# OpenBook_v3.net
KiCad netlist of a schematic drawn in EAGLE
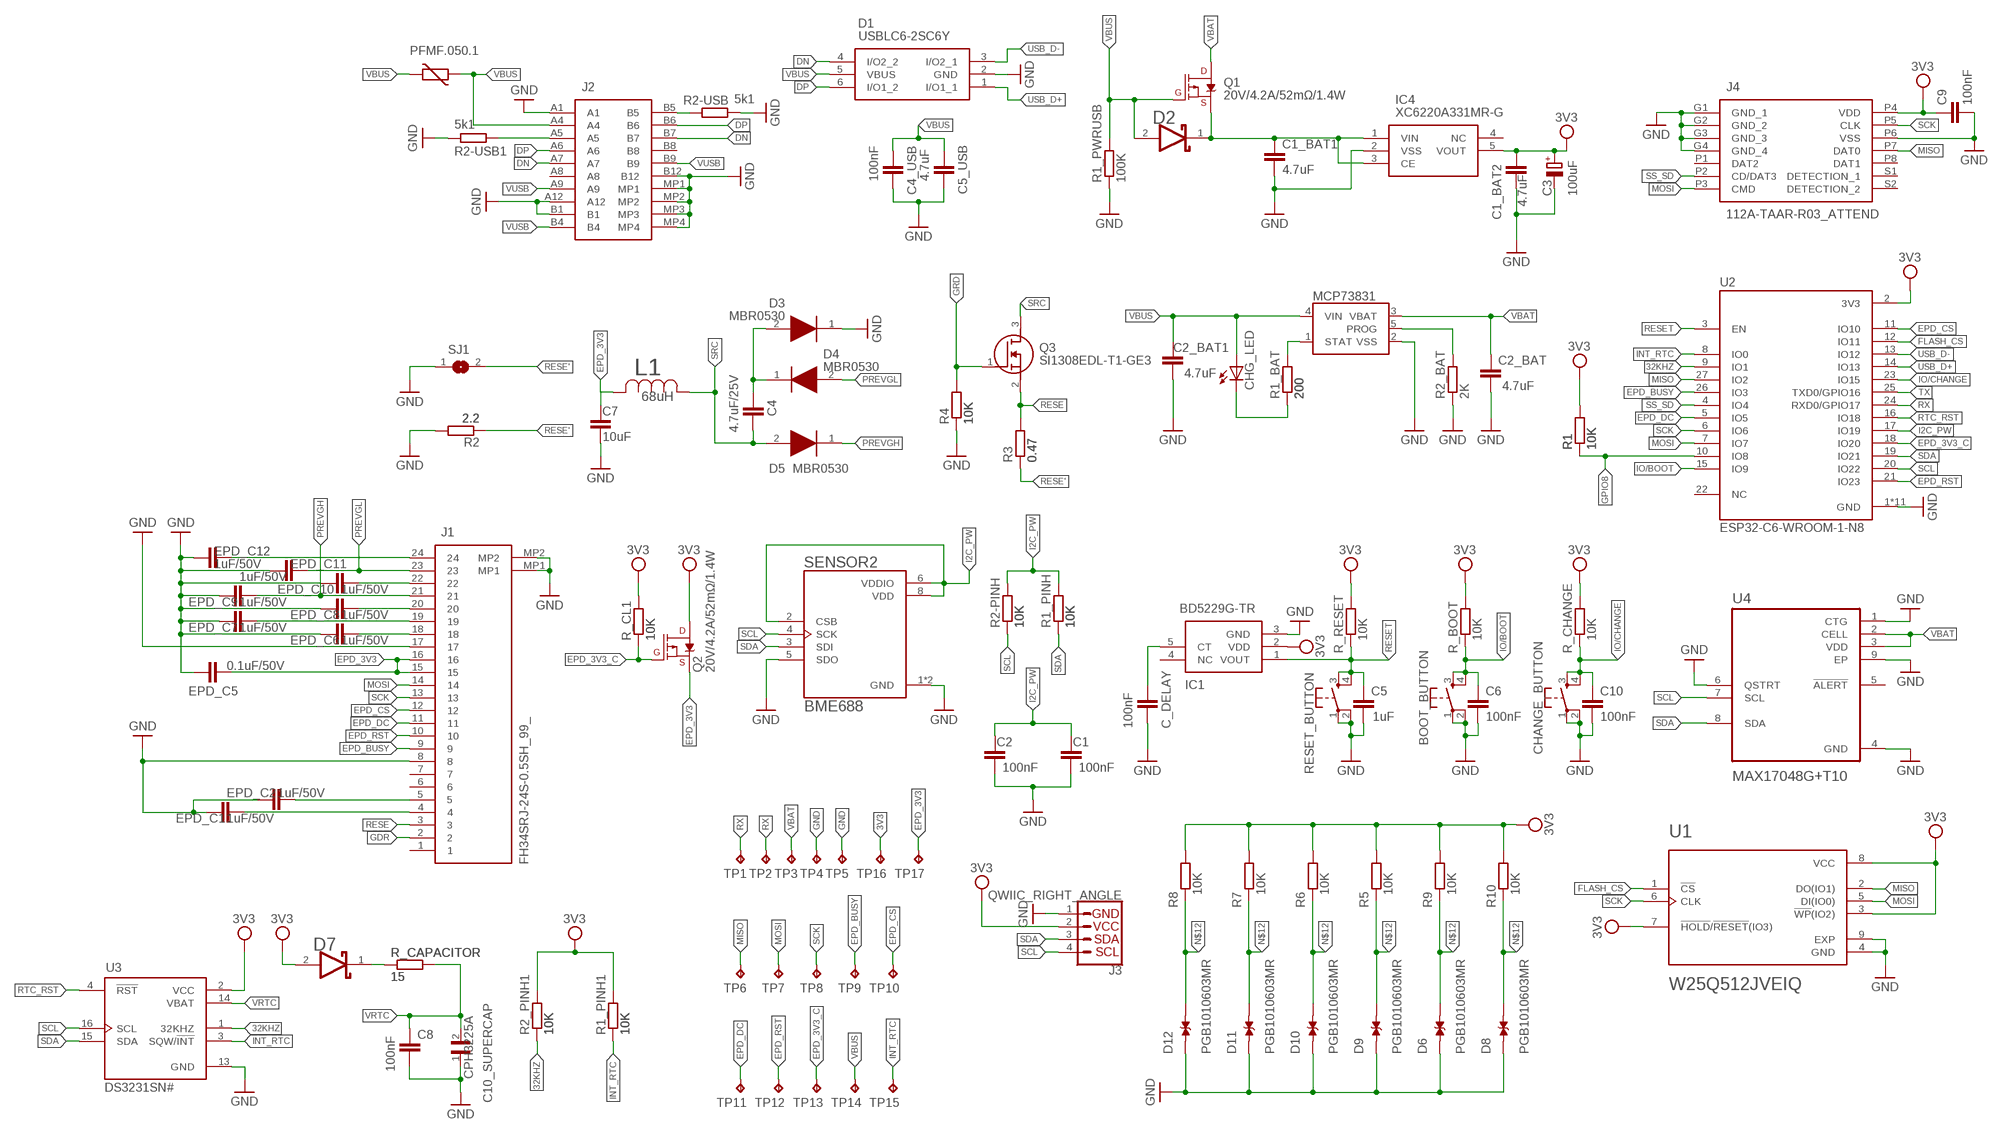
[diagram p0: schematic, sheet 1]

(export (version "E")
  (design (tool "Eeschema 10.0.6"))
  (components
    (comp (ref "BOOT_BUTTON")
      (value "BUTTON_CUSYOMV1")
      (footprint "eagle-import:MYBUTTON")
      (libsource (lib "eagle-import") (part "BUTTON_CUSYOMV1"))
    )
    (comp (ref "C1")
      (value "100nF")
      (footprint "eagle-import:ESP32_WROVER_EAGLE-LTSPICE_C0402")
      (libsource (lib "eagle-import") (part "ESP32_WROVER_EAGLE-LTSPICE_CC0402"))
    )
    (comp (ref "C1_BAT1")
      (value "4.7uF")
      (footprint "eagle-import:ESP32_WROVER_EAGLE-LTSPICE_C0402")
      (libsource (lib "eagle-import") (part "ESP32_WROVER_EAGLE-LTSPICE_CC0402"))
    )
    (comp (ref "C1_BAT2")
      (value "4.7uF")
      (footprint "eagle-import:ESP32_WROVER_EAGLE-LTSPICE_C0402")
      (libsource (lib "eagle-import") (part "ESP32_WROVER_EAGLE-LTSPICE_CC0402"))
    )
    (comp (ref "C2")
      (value "100nF")
      (footprint "eagle-import:ESP32_WROVER_EAGLE-LTSPICE_C0402")
      (libsource (lib "eagle-import") (part "ESP32_WROVER_EAGLE-LTSPICE_CC0402"))
    )
    (comp (ref "C2_BAT")
      (value "4.7uF")
      (footprint "eagle-import:ESP32_WROVER_EAGLE-LTSPICE_C0402")
      (libsource (lib "eagle-import") (part "ESP32_WROVER_EAGLE-LTSPICE_CC0402"))
    )
    (comp (ref "C2_BAT1")
      (value "4.7uF")
      (footprint "eagle-import:ESP32_WROVER_EAGLE-LTSPICE_C0402")
      (libsource (lib "eagle-import") (part "ESP32_WROVER_EAGLE-LTSPICE_CC0402"))
    )
    (comp (ref "C3")
      (value "100uF")
      (footprint "eagle-import:RCL_CT3528")
      (libsource (lib "eagle-import") (part "RCL_CPOL-EUCT3528"))
    )
    (comp (ref "C4")
      (value "4.7uF/25V")
      (footprint "eagle-import:ESP32_WROVER_EAGLE-LTSPICE_C0402")
      (libsource (lib "eagle-import") (part "ESP32_WROVER_EAGLE-LTSPICE_CC0402"))
    )
    (comp (ref "C4_USB")
      (value "100nF")
      (footprint "eagle-import:ESP32_WROVER_EAGLE-LTSPICE_C0402")
      (libsource (lib "eagle-import") (part "ESP32_WROVER_EAGLE-LTSPICE_CC0402"))
    )
    (comp (ref "C5")
      (value "1uF")
      (footprint "eagle-import:ESP32_WROVER_EAGLE-LTSPICE_C0402")
      (libsource (lib "eagle-import") (part "ESP32_WROVER_EAGLE-LTSPICE_CC0402"))
    )
    (comp (ref "C5_USB")
      (value "4.7uF")
      (footprint "eagle-import:ESP32_WROVER_EAGLE-LTSPICE_C0402")
      (libsource (lib "eagle-import") (part "ESP32_WROVER_EAGLE-LTSPICE_CC0402"))
    )
    (comp (ref "C6")
      (value "100nF")
      (footprint "eagle-import:ESP32_WROVER_EAGLE-LTSPICE_C0402")
      (libsource (lib "eagle-import") (part "ESP32_WROVER_EAGLE-LTSPICE_CC0402"))
    )
    (comp (ref "C7")
      (value "10uF")
      (footprint "eagle-import:ESP32_WROVER_EAGLE-LTSPICE_C0402")
      (libsource (lib "eagle-import") (part "ESP32_WROVER_EAGLE-LTSPICE_CC0402"))
    )
    (comp (ref "C8")
      (value "100nF")
      (footprint "eagle-import:ESP32_WROVER_EAGLE-LTSPICE_C0402")
      (libsource (lib "eagle-import") (part "ESP32_WROVER_EAGLE-LTSPICE_CC0402"))
    )
    (comp (ref "C9")
      (value "100nF")
      (footprint "eagle-import:ESP32_WROVER_EAGLE-LTSPICE_C0402")
      (libsource (lib "eagle-import") (part "ESP32_WROVER_EAGLE-LTSPICE_CC0402"))
    )
    (comp (ref "C10")
      (value "100nF")
      (footprint "eagle-import:ESP32_WROVER_EAGLE-LTSPICE_C0402")
      (libsource (lib "eagle-import") (part "ESP32_WROVER_EAGLE-LTSPICE_CC0402"))
    )
    (comp (ref "C10_SUPERCAP")
      (value "CPH3225A")
      (footprint "eagle-import:CAPCP3225X100N")
      (fields (field (name "MF") "Seiko Instruments"))
      (libsource (lib "eagle-import") (part "CPH3225A"))
    )
    (comp (ref "CHANGE_BUTTON")
      (value "BUTTON_CUSYOMV1")
      (footprint "eagle-import:MYBUTTON")
      (libsource (lib "eagle-import") (part "BUTTON_CUSYOMV1"))
    )
    (comp (ref "CHG_LED")
      (value "ADAFRUIT_LEDCHIP-LED0603")
      (footprint "eagle-import:ADAFRUIT_CHIP-LED0603")
      (libsource (lib "eagle-import") (part "ADAFRUIT_LEDCHIP-LED0603"))
    )
    (comp (ref "C_DELAY")
      (value "100nF")
      (footprint "eagle-import:ESP32_WROVER_EAGLE-LTSPICE_C0402")
      (libsource (lib "eagle-import") (part "ESP32_WROVER_EAGLE-LTSPICE_CC0402"))
    )
    (comp (ref "D1")
      (value "USBLC6-2SC6Y")
      (footprint "eagle-import:SOT95P280X145-6N")
      (fields (field (name "MF") "STMicroelectronics"))
      (libsource (lib "eagle-import") (part "USBLC6-2SC6Y"))
    )
    (comp (ref "D2")
      (value "ESP32_WROVER_AVX---SD0805S020S1R0_AVX_SD0805S020S1R0_0_0AVX_SD0805S020S1R0_0_0")
      (footprint "eagle-import:ESP32_WROVER_AVX---SD0805S020S1R0_AVX_SD0805S020S1R0_0")
      (fields
        (field (name "DIGIKEY_PART_NUMBER") "478-7800-1-ND")
        (field (name "MF") "AVX")
        (field (name "MOUSER_PART_NUMBER") "581-SD0805S020S1R0")
      )
      (libsource (lib "eagle-import") (part "ESP32_WROVER_AVX---SD0805S020S1R0_AVX_SD0805S020S1R0_0_0AVX_SD0805S020S1R0_0_0"))
    )
    (comp (ref "D3")
      (value "MBR0530")
      (footprint "eagle-import:SOD3716X135N")
      (fields (field (name "MF") "ON Semiconductor"))
      (libsource (lib "eagle-import") (part "MBR0530"))
    )
    (comp (ref "D4")
      (value "MBR0530")
      (footprint "eagle-import:SOD3716X135N")
      (fields (field (name "MF") "ON Semiconductor"))
      (libsource (lib "eagle-import") (part "MBR0530"))
    )
    (comp (ref "D5")
      (value "MBR0530")
      (footprint "eagle-import:SOD3716X135N")
      (fields (field (name "MF") "ON Semiconductor"))
      (libsource (lib "eagle-import") (part "MBR0530"))
    )
    (comp (ref "D6")
      (value "PGB1010603MR")
      (footprint "eagle-import:DIOC1608X36N")
      (fields (field (name "MF") "Littelfuse Inc."))
      (libsource (lib "eagle-import") (part "PGB1010603MR"))
    )
    (comp (ref "D7")
      (value "ESP32_WROVER_AVX---SD0805S020S1R0_AVX_SD0805S020S1R0_0_0AVX_SD0805S020S1R0_0_0")
      (footprint "eagle-import:ESP32_WROVER_AVX---SD0805S020S1R0_AVX_SD0805S020S1R0_0")
      (fields
        (field (name "DIGIKEY_PART_NUMBER") "478-7800-1-ND")
        (field (name "MF") "AVX")
        (field (name "MOUSER_PART_NUMBER") "581-SD0805S020S1R0")
      )
      (libsource (lib "eagle-import") (part "ESP32_WROVER_AVX---SD0805S020S1R0_AVX_SD0805S020S1R0_0_0AVX_SD0805S020S1R0_0_0"))
    )
    (comp (ref "D8")
      (value "PGB1010603MR")
      (footprint "eagle-import:DIOC1608X36N")
      (fields (field (name "MF") "Littelfuse Inc."))
      (libsource (lib "eagle-import") (part "PGB1010603MR"))
    )
    (comp (ref "D9")
      (value "PGB1010603MR")
      (footprint "eagle-import:DIOC1608X36N")
      (fields (field (name "MF") "Littelfuse Inc."))
      (libsource (lib "eagle-import") (part "PGB1010603MR"))
    )
    (comp (ref "D10")
      (value "PGB1010603MR")
      (footprint "eagle-import:DIOC1608X36N")
      (fields (field (name "MF") "Littelfuse Inc."))
      (libsource (lib "eagle-import") (part "PGB1010603MR"))
    )
    (comp (ref "D11")
      (value "PGB1010603MR")
      (footprint "eagle-import:DIOC1608X36N")
      (fields (field (name "MF") "Littelfuse Inc."))
      (libsource (lib "eagle-import") (part "PGB1010603MR"))
    )
    (comp (ref "D12")
      (value "PGB1010603MR")
      (footprint "eagle-import:DIOC1608X36N")
      (fields (field (name "MF") "Littelfuse Inc."))
      (libsource (lib "eagle-import") (part "PGB1010603MR"))
    )
    (comp (ref "EPD_C1")
      (value "1uF/50V")
      (footprint "eagle-import:ESP32_WROVER_EAGLE-LTSPICE_C0402")
      (libsource (lib "eagle-import") (part "ESP32_WROVER_EAGLE-LTSPICE_CC0402"))
    )
    (comp (ref "EPD_C2")
      (value "1uF/50V")
      (footprint "eagle-import:ESP32_WROVER_EAGLE-LTSPICE_C0402")
      (libsource (lib "eagle-import") (part "ESP32_WROVER_EAGLE-LTSPICE_CC0402"))
    )
    (comp (ref "EPD_C5")
      (value "0.1uF/50V")
      (footprint "eagle-import:ESP32_WROVER_EAGLE-LTSPICE_C0402")
      (libsource (lib "eagle-import") (part "ESP32_WROVER_EAGLE-LTSPICE_CC0402"))
    )
    (comp (ref "EPD_C6")
      (value "1uF/50V")
      (footprint "eagle-import:ESP32_WROVER_EAGLE-LTSPICE_C0402")
      (libsource (lib "eagle-import") (part "ESP32_WROVER_EAGLE-LTSPICE_CC0402"))
    )
    (comp (ref "EPD_C7")
      (value "1uF/50V")
      (footprint "eagle-import:ESP32_WROVER_EAGLE-LTSPICE_C0402")
      (libsource (lib "eagle-import") (part "ESP32_WROVER_EAGLE-LTSPICE_CC0402"))
    )
    (comp (ref "EPD_C8")
      (value "1uF/50V")
      (footprint "eagle-import:ESP32_WROVER_EAGLE-LTSPICE_C0402")
      (libsource (lib "eagle-import") (part "ESP32_WROVER_EAGLE-LTSPICE_CC0402"))
    )
    (comp (ref "EPD_C9")
      (value "1uF/50V")
      (footprint "eagle-import:ESP32_WROVER_EAGLE-LTSPICE_C0402")
      (libsource (lib "eagle-import") (part "ESP32_WROVER_EAGLE-LTSPICE_CC0402"))
    )
    (comp (ref "EPD_C10")
      (value "1uF/50V")
      (footprint "eagle-import:ESP32_WROVER_EAGLE-LTSPICE_C0402")
      (libsource (lib "eagle-import") (part "ESP32_WROVER_EAGLE-LTSPICE_CC0402"))
    )
    (comp (ref "EPD_C11")
      (value "1uF/50V")
      (footprint "eagle-import:ESP32_WROVER_EAGLE-LTSPICE_C0402")
      (libsource (lib "eagle-import") (part "ESP32_WROVER_EAGLE-LTSPICE_CC0402"))
    )
    (comp (ref "EPD_C12")
      (value "1uF/50V")
      (footprint "eagle-import:ESP32_WROVER_EAGLE-LTSPICE_C0402")
      (libsource (lib "eagle-import") (part "ESP32_WROVER_EAGLE-LTSPICE_CC0402"))
    )
    (comp (ref "IC1")
      (value "BD5229G-TR")
      (footprint "eagle-import:SOT95P280X125-5N")
      (fields (field (name "MOUSER_PART_NUMBER") "755-BD5229G-TR"))
      (libsource (lib "eagle-import") (part "BD5229G-TR"))
    )
    (comp (ref "IC4")
      (value "XC6220A331MR-G")
      (footprint "eagle-import:SOT95P280X120-5N")
      (fields (field (name "MOUSER_PART_NUMBER") "865-XC6220A331MR-G"))
      (libsource (lib "eagle-import") (part "XC6220A331MR-G"))
    )
    (comp (ref "J1")
      (value "FH34SRJ-24S-0.5SH_99_")
      (footprint "eagle-import:FH34SRJ24S05SH99")
      (fields
        (field (name "MANUFACTURER_PART_NUMBER") "FH34SRJ-24S-0.5SH(99)")
        (field (name "MOUSER_PART_NUMBER") "798-FH34SRJ24S05SH99")
      )
      (libsource (lib "eagle-import") (part "FH34SRJ-24S-0.5SH_99_"))
    )
    (comp (ref "J2")
      (value "SAMACSYS_PARTS_USB4110-GF-A")
      (footprint "eagle-import:SAMACSYS_PARTS_USB4110GFA")
      (fields
        (field (name "MANUFACTURER_PART_NUMBER") "USB4110-GF-A")
        (field (name "MOUSER_PART_NUMBER") "640-USB4110-GF-A")
      )
      (libsource (lib "eagle-import") (part "SAMACSYS_PARTS_USB4110-GF-A"))
    )
    (comp (ref "J3")
      (value "QWIIC_RIGHT_ANGLE")
      (footprint "eagle-import:JST04_1MM_RA")
      (libsource (lib "eagle-import") (part "QWIIC_CONNECTORJS-1MM"))
    )
    (comp (ref "J4")
      (value "112A-TAAR-R03_ATTEND")
      (footprint "eagle-import:112ATAARR03ATTEND")
      (fields (field (name "MANUFACTURER_PART_NUMBER") "112A-TAAR-R03 ATTEND"))
      (libsource (lib "eagle-import") (part "112A-TAAR-R03_ATTEND"))
    )
    (comp (ref "L1")
      (value "68uH")
      (footprint "eagle-import:IND_4828-WE-TPC_WRE")
      (fields
        (field (name "MANUFACTURER_PART_NUMBER") "744043680")
        (field (name "COPYRIGHT") "Copyright (C) 2024 Ultra Librarian. All rights reserved.")
      )
      (libsource (lib "eagle-import") (part "744043680IND_4828-WE-TPC_WRE"))
    )
    (comp (ref "MCP73831")
      (value "ESP32_WROVER_SPARKFUN-IC-POWER_MCP73831")
      (footprint "eagle-import:ESP32_WROVER_SPARKFUN-IC-POWER_SOT23-5")
      (libsource (lib "eagle-import") (part "ESP32_WROVER_SPARKFUN-IC-POWER_MCP73831"))
    )
    (comp (ref "PFMF.050.1")
      (value "ESP32C6_VARISTORCN1812")
      (footprint "eagle-import:ESP32C6_VARISTOR_CT_CN1812")
      (libsource (lib "eagle-import") (part "ESP32C6_VARISTORCN1812"))
    )
    (comp (ref "Q1")
      (value "20V/4.2A/52mΩ/1.4W")
      (footprint "eagle-import:ESP32_WROVER_SPARKFUN-DISCRETESEMI_SOT23-3")
      (libsource (lib "eagle-import") (part "ESP32_WROVER_SPARKFUN-DISCRETESEMI_MOSFET_PCH-DMG2305UX-7"))
    )
    (comp (ref "Q2")
      (value "20V/4.2A/52mΩ/1.4W")
      (footprint "eagle-import:ESP32_WROVER_SPARKFUN-DISCRETESEMI_SOT23-3")
      (libsource (lib "eagle-import") (part "ESP32_WROVER_SPARKFUN-DISCRETESEMI_MOSFET_PCH-DMG2305UX-7"))
    )
    (comp (ref "Q3")
      (value "SI1308EDL-T1-GE3")
      (footprint "eagle-import:SOT65P210X110-3N")
      (fields (field (name "MF") "Vishay Siliconix"))
      (libsource (lib "eagle-import") (part "SI1308EDL-T1-GE3"))
    )
    (comp (ref "R1")
      (value "10K")
      (footprint "eagle-import:ESP32_WROVER_EAGLE-LTSPICE_R0402")
      (libsource (lib "eagle-import") (part "ESP32_WROVER_EAGLE-LTSPICE_RR0402"))
    )
    (comp (ref "R1_BAT")
      (value "200")
      (footprint "eagle-import:ESP32_WROVER_EAGLE-LTSPICE_R0402")
      (libsource (lib "eagle-import") (part "ESP32_WROVER_EAGLE-LTSPICE_RR0402"))
    )
    (comp (ref "R1_PINH")
      (value "10K")
      (footprint "eagle-import:ESP32_WROVER_EAGLE-LTSPICE_R0402")
      (libsource (lib "eagle-import") (part "ESP32_WROVER_EAGLE-LTSPICE_RR0402"))
    )
    (comp (ref "R1_PINH1")
      (value "10K")
      (footprint "eagle-import:ESP32_WROVER_EAGLE-LTSPICE_R0402")
      (libsource (lib "eagle-import") (part "ESP32_WROVER_EAGLE-LTSPICE_RR0402"))
    )
    (comp (ref "R1_PWRUSB")
      (value "100K")
      (footprint "eagle-import:ESP32_WROVER_EAGLE-LTSPICE_R0402")
      (libsource (lib "eagle-import") (part "ESP32_WROVER_EAGLE-LTSPICE_RR0402"))
    )
    (comp (ref "R2")
      (value "2.2")
      (footprint "eagle-import:ESP32_WROVER_EAGLE-LTSPICE_R0402")
      (libsource (lib "eagle-import") (part "ESP32_WROVER_EAGLE-LTSPICE_RR0402"))
    )
    (comp (ref "R2-PINH")
      (value "10K")
      (footprint "eagle-import:ESP32_WROVER_EAGLE-LTSPICE_R0402")
      (libsource (lib "eagle-import") (part "ESP32_WROVER_EAGLE-LTSPICE_RR0402"))
    )
    (comp (ref "R2-USB")
      (value "5k1")
      (footprint "eagle-import:ESP32_WROVER_EAGLE-LTSPICE_R0402")
      (libsource (lib "eagle-import") (part "ESP32_WROVER_EAGLE-LTSPICE_RR0402"))
    )
    (comp (ref "R2-USB1")
      (value "5k1")
      (footprint "eagle-import:ESP32_WROVER_EAGLE-LTSPICE_R0402")
      (libsource (lib "eagle-import") (part "ESP32_WROVER_EAGLE-LTSPICE_RR0402"))
    )
    (comp (ref "R2_BAT")
      (value "2K")
      (footprint "eagle-import:ESP32_WROVER_EAGLE-LTSPICE_R0402")
      (libsource (lib "eagle-import") (part "ESP32_WROVER_EAGLE-LTSPICE_RR0402"))
    )
    (comp (ref "R2_PINH1")
      (value "10K")
      (footprint "eagle-import:ESP32_WROVER_EAGLE-LTSPICE_R0402")
      (libsource (lib "eagle-import") (part "ESP32_WROVER_EAGLE-LTSPICE_RR0402"))
    )
    (comp (ref "R3")
      (value "0.47")
      (footprint "eagle-import:ESP32_WROVER_EAGLE-LTSPICE_R0402")
      (libsource (lib "eagle-import") (part "ESP32_WROVER_EAGLE-LTSPICE_RR0402"))
    )
    (comp (ref "R4")
      (value "10K")
      (footprint "eagle-import:ESP32_WROVER_EAGLE-LTSPICE_R0402")
      (libsource (lib "eagle-import") (part "ESP32_WROVER_EAGLE-LTSPICE_RR0402"))
    )
    (comp (ref "R5")
      (value "10K")
      (footprint "eagle-import:ESP32_WROVER_EAGLE-LTSPICE_R0402")
      (libsource (lib "eagle-import") (part "ESP32_WROVER_EAGLE-LTSPICE_RR0402"))
    )
    (comp (ref "R6")
      (value "10K")
      (footprint "eagle-import:ESP32_WROVER_EAGLE-LTSPICE_R0402")
      (libsource (lib "eagle-import") (part "ESP32_WROVER_EAGLE-LTSPICE_RR0402"))
    )
    (comp (ref "R7")
      (value "10K")
      (footprint "eagle-import:ESP32_WROVER_EAGLE-LTSPICE_R0402")
      (libsource (lib "eagle-import") (part "ESP32_WROVER_EAGLE-LTSPICE_RR0402"))
    )
    (comp (ref "R8")
      (value "10K")
      (footprint "eagle-import:ESP32_WROVER_EAGLE-LTSPICE_R0402")
      (libsource (lib "eagle-import") (part "ESP32_WROVER_EAGLE-LTSPICE_RR0402"))
    )
    (comp (ref "R9")
      (value "10K")
      (footprint "eagle-import:ESP32_WROVER_EAGLE-LTSPICE_R0402")
      (libsource (lib "eagle-import") (part "ESP32_WROVER_EAGLE-LTSPICE_RR0402"))
    )
    (comp (ref "R10")
      (value "10K")
      (footprint "eagle-import:ESP32_WROVER_EAGLE-LTSPICE_R0402")
      (libsource (lib "eagle-import") (part "ESP32_WROVER_EAGLE-LTSPICE_RR0402"))
    )
    (comp (ref "RESET_BUTTON")
      (value "BUTTON_CUSYOMV1")
      (footprint "eagle-import:MYBUTTON")
      (libsource (lib "eagle-import") (part "BUTTON_CUSYOMV1"))
    )
    (comp (ref "R_BOOT")
      (value "10K")
      (footprint "eagle-import:ESP32_WROVER_EAGLE-LTSPICE_R0402")
      (libsource (lib "eagle-import") (part "ESP32_WROVER_EAGLE-LTSPICE_RR0402"))
    )
    (comp (ref "R_CAPACITOR")
      (value "15")
      (footprint "eagle-import:ESP32_WROVER_EAGLE-LTSPICE_R0402")
      (libsource (lib "eagle-import") (part "ESP32_WROVER_EAGLE-LTSPICE_RR0402"))
    )
    (comp (ref "R_CHANGE")
      (value "10K")
      (footprint "eagle-import:ESP32_WROVER_EAGLE-LTSPICE_R0402")
      (libsource (lib "eagle-import") (part "ESP32_WROVER_EAGLE-LTSPICE_RR0402"))
    )
    (comp (ref "R_CL1")
      (value "10K")
      (footprint "eagle-import:ESP32_WROVER_EAGLE-LTSPICE_R0402")
      (libsource (lib "eagle-import") (part "ESP32_WROVER_EAGLE-LTSPICE_RR0402"))
    )
    (comp (ref "R_RESET")
      (value "10K")
      (footprint "eagle-import:ESP32_WROVER_EAGLE-LTSPICE_R0402")
      (libsource (lib "eagle-import") (part "ESP32_WROVER_EAGLE-LTSPICE_RR0402"))
    )
    (comp (ref "SENSOR2")
      (value "BME688")
      (footprint "eagle-import:ESP32_WROVER_BME680_PSON80P300X300X100-8N")
      (fields (field (name "MF") "Bosch Sensortec") (field (name "MP") "BME680"))
      (libsource (lib "eagle-import") (part "ESP32_WROVER_BME680_BME680"))
    )
    (comp (ref "SJ1") (value "SJ") (footprint "eagle-import:SJ") (libsource (lib "eagle-import") (part "SJ")))
    (comp (ref "TP1")
      (value "TPTP20R")
      (footprint "eagle-import:TP20R")
      (libsource (lib "eagle-import") (part "TPTP20R"))
    )
    (comp (ref "TP2")
      (value "TPTP20R")
      (footprint "eagle-import:TP20R")
      (libsource (lib "eagle-import") (part "TPTP20R"))
    )
    (comp (ref "TP3")
      (value "TPTP20R")
      (footprint "eagle-import:TP20R")
      (libsource (lib "eagle-import") (part "TPTP20R"))
    )
    (comp (ref "TP4")
      (value "TPTP20R")
      (footprint "eagle-import:TP20R")
      (libsource (lib "eagle-import") (part "TPTP20R"))
    )
    (comp (ref "TP5")
      (value "TPTP20R")
      (footprint "eagle-import:TP20R")
      (libsource (lib "eagle-import") (part "TPTP20R"))
    )
    (comp (ref "TP6")
      (value "TPTP20R")
      (footprint "eagle-import:TP20R")
      (libsource (lib "eagle-import") (part "TPTP20R"))
    )
    (comp (ref "TP7")
      (value "TPTP20R")
      (footprint "eagle-import:TP20R")
      (libsource (lib "eagle-import") (part "TPTP20R"))
    )
    (comp (ref "TP8")
      (value "TPTP20R")
      (footprint "eagle-import:TP20R")
      (libsource (lib "eagle-import") (part "TPTP20R"))
    )
    (comp (ref "TP9")
      (value "TPTP20R")
      (footprint "eagle-import:TP20R")
      (libsource (lib "eagle-import") (part "TPTP20R"))
    )
    (comp (ref "TP10")
      (value "TPTP20R")
      (footprint "eagle-import:TP20R")
      (libsource (lib "eagle-import") (part "TPTP20R"))
    )
    (comp (ref "TP11")
      (value "TPTP20R")
      (footprint "eagle-import:TP20R")
      (libsource (lib "eagle-import") (part "TPTP20R"))
    )
    (comp (ref "TP12")
      (value "TPTP20R")
      (footprint "eagle-import:TP20R")
      (libsource (lib "eagle-import") (part "TPTP20R"))
    )
    (comp (ref "TP13")
      (value "TPTP20R")
      (footprint "eagle-import:TP20R")
      (libsource (lib "eagle-import") (part "TPTP20R"))
    )
    (comp (ref "TP14")
      (value "TPTP20R")
      (footprint "eagle-import:TP20R")
      (libsource (lib "eagle-import") (part "TPTP20R"))
    )
    (comp (ref "TP15")
      (value "TPTP20R")
      (footprint "eagle-import:TP20R")
      (libsource (lib "eagle-import") (part "TPTP20R"))
    )
    (comp (ref "TP16")
      (value "TPTP20R")
      (footprint "eagle-import:TP20R")
      (libsource (lib "eagle-import") (part "TPTP20R"))
    )
    (comp (ref "TP17")
      (value "TPTP20R")
      (footprint "eagle-import:TP20R")
      (libsource (lib "eagle-import") (part "TPTP20R"))
    )
    (comp (ref "U1")
      (value "W25Q512JVEIQ")
      (footprint "eagle-import:SON127P600X800X80-9N")
      (fields (field (name "MF") "Winbond Electronics"))
      (libsource (lib "eagle-import") (part "W25Q512JVEIQ"))
    )
    (comp (ref "U2")
      (value "ESP32-C6-WROOM-1-N8")
      (footprint "eagle-import:XCVR_ESP32-C6-WROOM-1-N8")
      (fields (field (name "MF") "Espressif Systems"))
      (libsource (lib "eagle-import") (part "ESP32-C6-WROOM-1-N8"))
    )
    (comp (ref "U3")
      (value "DS3231SN#")
      (footprint "eagle-import:SOIC127P1032X265-16N")
      (fields (field (name "MF") "Analog Devices"))
      (libsource (lib "eagle-import") (part "DS3231SN#"))
    )
    (comp (ref "U4")
      (value "MAX17048G+T10")
      (footprint "eagle-import:SON50P200X200X80-9N")
      (fields (field (name "MF") "Analog Devices"))
      (libsource (lib "eagle-import") (part "MAX17048G+T10"))
    )
  )
  (nets
    (net (code "1") (name "3V3") (class "Default")
      (node (ref "C1_BAT2") (pin "1") (pinfunction "1_1") (pintype "passive"))
      (node (ref "C3") (pin "+") (pinfunction "+_+") (pintype "passive"))
      (node (ref "C9") (pin "1") (pinfunction "1_1") (pintype "passive"))
      (node (ref "D7") (pin "2") (pinfunction "ANODE_2") (pintype "bidirectional"))
      (node (ref "IC1") (pin "2") (pinfunction "VDD_2") (pintype "bidirectional"))
      (node (ref "IC4") (pin "5") (pinfunction "VOUT_5") (pintype "bidirectional"))
      (node (ref "J3") (pin "2") (pinfunction "2_2") (pintype "power_in"))
      (node (ref "J4") (pin "P4") (pinfunction "VDD_P4") (pintype "bidirectional"))
      (node (ref "Q2") (pin "3") (pinfunction "D_3") (pintype "bidirectional"))
      (node (ref "R1") (pin "2") (pinfunction "2_2") (pintype "passive"))
      (node (ref "R10") (pin "2") (pinfunction "2_2") (pintype "passive"))
      (node (ref "R1_PINH1") (pin "2") (pinfunction "2_2") (pintype "passive"))
      (node (ref "R2_PINH1") (pin "2") (pinfunction "2_2") (pintype "passive"))
      (node (ref "R5") (pin "2") (pinfunction "2_2") (pintype "passive"))
      (node (ref "R6") (pin "2") (pinfunction "2_2") (pintype "passive"))
      (node (ref "R7") (pin "2") (pinfunction "2_2") (pintype "passive"))
      (node (ref "R8") (pin "2") (pinfunction "2_2") (pintype "passive"))
      (node (ref "R9") (pin "2") (pinfunction "2_2") (pintype "passive"))
      (node (ref "R_BOOT") (pin "2") (pinfunction "2_2") (pintype "passive"))
      (node (ref "R_CHANGE") (pin "2") (pinfunction "2_2") (pintype "passive"))
      (node (ref "R_CL1") (pin "2") (pinfunction "2_2") (pintype "passive"))
      (node (ref "R_RESET") (pin "2") (pinfunction "2_2") (pintype "passive"))
      (node (ref "TP16") (pin "TP") (pinfunction "TP_TP") (pintype "input"))
      (node (ref "U1") (pin "3") (pinfunction "~{WP}(IO2)_3") (pintype "bidirectional"))
      (node (ref "U1") (pin "7") (pinfunction "~{HOLD}/~{RESET}(IO3)_7") (pintype "bidirectional"))
      (node (ref "U1") (pin "8") (pinfunction "VCC_8") (pintype "power_in"))
      (node (ref "U2") (pin "2") (pinfunction "3V3_2") (pintype "power_in"))
      (node (ref "U3") (pin "2") (pinfunction "VCC_2") (pintype "power_in"))
    )
    (net (code "2") (name "32KHZ") (class "Default")
      (node (ref "R2_PINH1") (pin "1") (pinfunction "1_1") (pintype "passive"))
      (node (ref "U2") (pin "9") (pinfunction "IO1_9") (pintype "bidirectional"))
      (node (ref "U3") (pin "1") (pinfunction "32KHZ_1") (pintype "output"))
    )
    (net (code "3") (name "DN") (class "Default")
      (node (ref "D1") (pin "4") (pinfunction "I/O2_2_4") (pintype "bidirectional"))
      (node (ref "J2") (pin "A7") (pinfunction "A7_A7") (pintype "bidirectional"))
      (node (ref "J2") (pin "B7") (pinfunction "B7_B7") (pintype "bidirectional"))
    )
    (net (code "4") (name "DP") (class "Default")
      (node (ref "D1") (pin "6") (pinfunction "I/O1_2_6") (pintype "bidirectional"))
      (node (ref "J2") (pin "A6") (pinfunction "A6_A6") (pintype "bidirectional"))
      (node (ref "J2") (pin "B6") (pinfunction "B6_B6") (pintype "bidirectional"))
    )
    (net (code "5") (name "EPD_3V3") (class "Default")
      (node (ref "C7") (pin "1") (pinfunction "1_1") (pintype "passive"))
      (node (ref "EPD_C5") (pin "2") (pinfunction "2_2") (pintype "passive"))
      (node (ref "J1") (pin "15") (pinfunction "15_15") (pintype "bidirectional"))
      (node (ref "J1") (pin "16") (pinfunction "16_16") (pintype "bidirectional"))
      (node (ref "L1") (pin "2") (pinfunction "2_2") (pintype "passive"))
      (node (ref "Q2") (pin "2") (pinfunction "S_2") (pintype "bidirectional"))
      (node (ref "TP17") (pin "TP") (pinfunction "TP_TP") (pintype "input"))
    )
    (net (code "6") (name "EPD_3V3_C") (class "Default")
      (node (ref "Q2") (pin "1") (pinfunction "G_1") (pintype "bidirectional"))
      (node (ref "R_CL1") (pin "1") (pinfunction "1_1") (pintype "passive"))
      (node (ref "TP13") (pin "TP") (pinfunction "TP_TP") (pintype "input"))
      (node (ref "U2") (pin "18") (pinfunction "IO20_18") (pintype "bidirectional"))
    )
    (net (code "7") (name "EPD_BUSY") (class "Default")
      (node (ref "J1") (pin "9") (pinfunction "9_9") (pintype "bidirectional"))
      (node (ref "TP9") (pin "TP") (pinfunction "TP_TP") (pintype "input"))
      (node (ref "U2") (pin "26") (pinfunction "IO3_26") (pintype "bidirectional"))
    )
    (net (code "8") (name "EPD_CS") (class "Default")
      (node (ref "J1") (pin "12") (pinfunction "12_12") (pintype "bidirectional"))
      (node (ref "TP10") (pin "TP") (pinfunction "TP_TP") (pintype "input"))
      (node (ref "U2") (pin "11") (pinfunction "IO10_11") (pintype "bidirectional"))
    )
    (net (code "9") (name "EPD_DC") (class "Default")
      (node (ref "J1") (pin "11") (pinfunction "11_11") (pintype "bidirectional"))
      (node (ref "TP11") (pin "TP") (pinfunction "TP_TP") (pintype "input"))
      (node (ref "U2") (pin "5") (pinfunction "IO5_5") (pintype "bidirectional"))
    )
    (net (code "10") (name "EPD_RST") (class "Default")
      (node (ref "J1") (pin "10") (pinfunction "10_10") (pintype "bidirectional"))
      (node (ref "TP12") (pin "TP") (pinfunction "TP_TP") (pintype "input"))
      (node (ref "U2") (pin "21") (pinfunction "IO23_21") (pintype "bidirectional"))
    )
    (net (code "11") (name "FLASH_CS") (class "Default")
      (node (ref "U1") (pin "1") (pinfunction "~{CS}_1") (pintype "input"))
      (node (ref "U2") (pin "12") (pinfunction "IO11_12") (pintype "bidirectional"))
    )
    (net (code "12") (name "GDR") (class "Default")
      (node (ref "J1") (pin "2") (pinfunction "2_2") (pintype "bidirectional"))
    )
    (net (code "13") (name "GND") (class "Default")
      (node (ref "BOOT_BUTTON") (pin "1") (pinfunction "1_1") (pintype "passive"))
      (node (ref "BOOT_BUTTON") (pin "2") (pinfunction "2_2") (pintype "passive"))
      (node (ref "C1") (pin "2") (pinfunction "2_2") (pintype "passive"))
      (node (ref "C10") (pin "2") (pinfunction "2_2") (pintype "passive"))
      (node (ref "C10_SUPERCAP") (pin "1") (pinfunction "1_1") (pintype "passive"))
      (node (ref "C1_BAT1") (pin "2") (pinfunction "2_2") (pintype "passive"))
      (node (ref "C1_BAT2") (pin "2") (pinfunction "2_2") (pintype "passive"))
      (node (ref "C2") (pin "2") (pinfunction "2_2") (pintype "passive"))
      (node (ref "C2_BAT") (pin "2") (pinfunction "2_2") (pintype "passive"))
      (node (ref "C2_BAT1") (pin "2") (pinfunction "2_2") (pintype "passive"))
      (node (ref "C3") (pin "-") (pinfunction "-_-") (pintype "passive"))
      (node (ref "C4_USB") (pin "2") (pinfunction "2_2") (pintype "passive"))
      (node (ref "C5") (pin "2") (pinfunction "2_2") (pintype "passive"))
      (node (ref "C5_USB") (pin "2") (pinfunction "2_2") (pintype "passive"))
      (node (ref "C6") (pin "2") (pinfunction "2_2") (pintype "passive"))
      (node (ref "C7") (pin "2") (pinfunction "2_2") (pintype "passive"))
      (node (ref "C8") (pin "2") (pinfunction "2_2") (pintype "passive"))
      (node (ref "C9") (pin "2") (pinfunction "2_2") (pintype "passive"))
      (node (ref "CHANGE_BUTTON") (pin "1") (pinfunction "1_1") (pintype "passive"))
      (node (ref "CHANGE_BUTTON") (pin "2") (pinfunction "2_2") (pintype "passive"))
      (node (ref "C_DELAY") (pin "2") (pinfunction "2_2") (pintype "passive"))
      (node (ref "D1") (pin "2") (pinfunction "GND_2") (pintype "bidirectional"))
      (node (ref "D10") (pin "1") (pinfunction "1_1") (pintype "passive"))
      (node (ref "D11") (pin "1") (pinfunction "1_1") (pintype "passive"))
      (node (ref "D12") (pin "1") (pinfunction "1_1") (pintype "passive"))
      (node (ref "D3") (pin "1") (pinfunction "K_1") (pintype "bidirectional"))
      (node (ref "D6") (pin "1") (pinfunction "1_1") (pintype "passive"))
      (node (ref "D8") (pin "1") (pinfunction "1_1") (pintype "passive"))
      (node (ref "D9") (pin "1") (pinfunction "1_1") (pintype "passive"))
      (node (ref "EPD_C1") (pin "1") (pinfunction "1_1") (pintype "passive"))
      (node (ref "EPD_C10") (pin "1") (pinfunction "1_1") (pintype "passive"))
      (node (ref "EPD_C11") (pin "1") (pinfunction "1_1") (pintype "passive"))
      (node (ref "EPD_C12") (pin "1") (pinfunction "1_1") (pintype "passive"))
      (node (ref "EPD_C2") (pin "1") (pinfunction "1_1") (pintype "passive"))
      (node (ref "EPD_C5") (pin "1") (pinfunction "1_1") (pintype "passive"))
      (node (ref "EPD_C6") (pin "1") (pinfunction "1_1") (pintype "passive"))
      (node (ref "EPD_C7") (pin "1") (pinfunction "1_1") (pintype "passive"))
      (node (ref "EPD_C8") (pin "1") (pinfunction "1_1") (pintype "passive"))
      (node (ref "EPD_C9") (pin "1") (pinfunction "1_1") (pintype "passive"))
      (node (ref "IC1") (pin "3") (pinfunction "GND_3") (pintype "bidirectional"))
      (node (ref "IC4") (pin "2") (pinfunction "VSS_2") (pintype "bidirectional"))
      (node (ref "J1") (pin "17") (pinfunction "17_17") (pintype "bidirectional"))
      (node (ref "J1") (pin "8") (pinfunction "8_8") (pintype "bidirectional"))
      (node (ref "J1") (pin "MP1") (pinfunction "MP1_MP1") (pintype "bidirectional"))
      (node (ref "J1") (pin "MP2") (pinfunction "MP2_MP2") (pintype "bidirectional"))
      (node (ref "J2") (pin "A1") (pinfunction "A1_A1") (pintype "bidirectional"))
      (node (ref "J2") (pin "A12") (pinfunction "A12_A12") (pintype "bidirectional"))
      (node (ref "J2") (pin "B1") (pinfunction "B1_B1") (pintype "bidirectional"))
      (node (ref "J2") (pin "B12") (pinfunction "B12_B12") (pintype "bidirectional"))
      (node (ref "J2") (pin "MP1") (pinfunction "MP1_MP1") (pintype "bidirectional"))
      (node (ref "J2") (pin "MP2") (pinfunction "MP2_MP2") (pintype "bidirectional"))
      (node (ref "J2") (pin "MP3") (pinfunction "MP3_MP3") (pintype "bidirectional"))
      (node (ref "J2") (pin "MP4") (pinfunction "MP4_MP4") (pintype "bidirectional"))
      (node (ref "J3") (pin "1") (pinfunction "1_1") (pintype "power_in"))
      (node (ref "J4") (pin "G1") (pinfunction "GND_1_G1") (pintype "bidirectional"))
      (node (ref "J4") (pin "G2") (pinfunction "GND_2_G2") (pintype "bidirectional"))
      (node (ref "J4") (pin "G3") (pinfunction "GND_3_G3") (pintype "bidirectional"))
      (node (ref "J4") (pin "G4") (pinfunction "GND_4_G4") (pintype "bidirectional"))
      (node (ref "J4") (pin "P6") (pinfunction "VSS_P6") (pintype "bidirectional"))
      (node (ref "MCP73831") (pin "2") (pinfunction "VSS_2") (pintype "power_in"))
      (node (ref "R1_PWRUSB") (pin "1") (pinfunction "1_1") (pintype "passive"))
      (node (ref "R2") (pin "2") (pinfunction "2_2") (pintype "passive"))
      (node (ref "R2-USB") (pin "2") (pinfunction "2_2") (pintype "passive"))
      (node (ref "R2-USB1") (pin "1") (pinfunction "1_1") (pintype "passive"))
      (node (ref "R2_BAT") (pin "1") (pinfunction "1_1") (pintype "passive"))
      (node (ref "R4") (pin "1") (pinfunction "1_1") (pintype "passive"))
      (node (ref "RESET_BUTTON") (pin "1") (pinfunction "1_1") (pintype "passive"))
      (node (ref "RESET_BUTTON") (pin "2") (pinfunction "2_2") (pintype "passive"))
      (node (ref "SENSOR2") (pin "1") (pinfunction "GND_1") (pintype "power_in"))
      (node (ref "SENSOR2") (pin "5") (pinfunction "SDO_5") (pintype "bidirectional"))
      (node (ref "SENSOR2") (pin "7") (pinfunction "GND_7") (pintype "power_in"))
      (node (ref "SJ1") (pin "1") (pinfunction "1_1") (pintype "passive"))
      (node (ref "TP4") (pin "TP") (pinfunction "TP_TP") (pintype "input"))
      (node (ref "TP5") (pin "TP") (pinfunction "TP_TP") (pintype "input"))
      (node (ref "U1") (pin "4") (pinfunction "GND_4") (pintype "power_in"))
      (node (ref "U1") (pin "9") (pinfunction "EXP_9") (pintype "passive"))
      (node (ref "U2") (pin "1") (pinfunction "GND_1") (pintype "power_in"))
      (node (ref "U2") (pin "28") (pinfunction "GND_28") (pintype "power_in"))
      (node (ref "U2") (pin "29_1") (pinfunction "GND_29_1") (pintype "power_in"))
      (node (ref "U2") (pin "29_2") (pinfunction "GND_29_2") (pintype "power_in"))
      (node (ref "U2") (pin "29_3") (pinfunction "GND_29_3") (pintype "power_in"))
      (node (ref "U2") (pin "29_4") (pinfunction "GND_29_4") (pintype "power_in"))
      (node (ref "U2") (pin "29_5") (pinfunction "GND_29_5") (pintype "power_in"))
      (node (ref "U2") (pin "29_6") (pinfunction "GND_29_6") (pintype "power_in"))
      (node (ref "U2") (pin "29_7") (pinfunction "GND_29_7") (pintype "power_in"))
      (node (ref "U2") (pin "29_8") (pinfunction "GND_29_8") (pintype "power_in"))
      (node (ref "U2") (pin "29_9") (pinfunction "GND_29_9") (pintype "power_in"))
      (node (ref "U3") (pin "13") (pinfunction "GND_13") (pintype "power_in"))
      (node (ref "U4") (pin "1") (pinfunction "CTG_1") (pintype "power_in"))
      (node (ref "U4") (pin "4") (pinfunction "GND_4") (pintype "power_in"))
      (node (ref "U4") (pin "6") (pinfunction "QSTRT_6") (pintype "input"))
      (node (ref "U4") (pin "9") (pinfunction "EP_9") (pintype "power_in"))
    )
    (net (code "14") (name "GPIO8") (class "Default")
      (node (ref "R1") (pin "1") (pinfunction "1_1") (pintype "passive"))
      (node (ref "U2") (pin "10") (pinfunction "IO8_10") (pintype "bidirectional"))
    )
    (net (code "15") (name "GRD") (class "Default")
      (node (ref "Q3") (pin "1") (pinfunction "G_1") (pintype "bidirectional"))
      (node (ref "R4") (pin "2") (pinfunction "2_2") (pintype "passive"))
    )
    (net (code "16") (name "I2C_PW") (class "Default")
      (node (ref "C1") (pin "1") (pinfunction "1_1") (pintype "passive"))
      (node (ref "C2") (pin "1") (pinfunction "1_1") (pintype "passive"))
      (node (ref "R1_PINH") (pin "2") (pinfunction "2_2") (pintype "passive"))
      (node (ref "R2-PINH") (pin "2") (pinfunction "2_2") (pintype "passive"))
      (node (ref "SENSOR2") (pin "2") (pinfunction "CSB_2") (pintype "input"))
      (node (ref "SENSOR2") (pin "6") (pinfunction "VDDIO_6") (pintype "power_in"))
      (node (ref "SENSOR2") (pin "8") (pinfunction "VDD_8") (pintype "power_in"))
      (node (ref "U2") (pin "17") (pinfunction "IO19_17") (pintype "bidirectional"))
    )
    (net (code "17") (name "INT_RTC") (class "Default")
      (node (ref "R1_PINH1") (pin "1") (pinfunction "1_1") (pintype "passive"))
      (node (ref "TP15") (pin "TP") (pinfunction "TP_TP") (pintype "input"))
      (node (ref "U2") (pin "8") (pinfunction "IO0_8") (pintype "bidirectional"))
      (node (ref "U3") (pin "3") (pinfunction "SQW/~{INT}_3") (pintype "output"))
    )
    (net (code "18") (name "IO{slash}BOOT") (class "Default")
      (node (ref "BOOT_BUTTON") (pin "3") (pinfunction "3_3") (pintype "passive"))
      (node (ref "BOOT_BUTTON") (pin "4") (pinfunction "4_4") (pintype "passive"))
      (node (ref "C6") (pin "1") (pinfunction "1_1") (pintype "passive"))
      (node (ref "R_BOOT") (pin "1") (pinfunction "1_1") (pintype "passive"))
      (node (ref "U2") (pin "15") (pinfunction "IO9_15") (pintype "bidirectional"))
    )
    (net (code "19") (name "IO{slash}CHANGE") (class "Default")
      (node (ref "C10") (pin "1") (pinfunction "1_1") (pintype "passive"))
      (node (ref "CHANGE_BUTTON") (pin "3") (pinfunction "3_3") (pintype "passive"))
      (node (ref "CHANGE_BUTTON") (pin "4") (pinfunction "4_4") (pintype "passive"))
      (node (ref "R_CHANGE") (pin "1") (pinfunction "1_1") (pintype "passive"))
      (node (ref "U2") (pin "23") (pinfunction "IO15_23") (pintype "bidirectional"))
    )
    (net (code "20") (name "MISO") (class "Default")
      (node (ref "J4") (pin "P7") (pinfunction "DAT0_P7") (pintype "bidirectional"))
      (node (ref "TP6") (pin "TP") (pinfunction "TP_TP") (pintype "input"))
      (node (ref "U1") (pin "2") (pinfunction "DO(IO1)_2") (pintype "bidirectional"))
      (node (ref "U2") (pin "27") (pinfunction "IO2_27") (pintype "bidirectional"))
    )
    (net (code "21") (name "MOSI") (class "Default")
      (node (ref "J1") (pin "14") (pinfunction "14_14") (pintype "bidirectional"))
      (node (ref "J4") (pin "P3") (pinfunction "CMD_P3") (pintype "bidirectional"))
      (node (ref "TP7") (pin "TP") (pinfunction "TP_TP") (pintype "input"))
      (node (ref "U1") (pin "5") (pinfunction "DI(IO0)_5") (pintype "bidirectional"))
      (node (ref "U2") (pin "7") (pinfunction "IO7_7") (pintype "bidirectional"))
    )
    (net (code "22") (name "N$12") (class "Default")
      (node (ref "D10") (pin "2") (pinfunction "2_2") (pintype "passive"))
      (node (ref "D11") (pin "2") (pinfunction "2_2") (pintype "passive"))
      (node (ref "D12") (pin "2") (pinfunction "2_2") (pintype "passive"))
      (node (ref "D6") (pin "2") (pinfunction "2_2") (pintype "passive"))
      (node (ref "D8") (pin "2") (pinfunction "2_2") (pintype "passive"))
      (node (ref "D9") (pin "2") (pinfunction "2_2") (pintype "passive"))
      (node (ref "R10") (pin "1") (pinfunction "1_1") (pintype "passive"))
      (node (ref "R5") (pin "1") (pinfunction "1_1") (pintype "passive"))
      (node (ref "R6") (pin "1") (pinfunction "1_1") (pintype "passive"))
      (node (ref "R7") (pin "1") (pinfunction "1_1") (pintype "passive"))
      (node (ref "R8") (pin "1") (pinfunction "1_1") (pintype "passive"))
      (node (ref "R9") (pin "1") (pinfunction "1_1") (pintype "passive"))
    )
    (net (code "23") (name "Net-(CHG_LED-PadC)") (class "Default")
      (node (ref "CHG_LED") (pin "C") (pinfunction "C_C") (pintype "passive"))
      (node (ref "R1_BAT") (pin "1") (pinfunction "1_1") (pintype "passive"))
    )
    (net (code "24") (name "Net-(D2-CATHODE)") (class "Default")
      (node (ref "C1_BAT1") (pin "1") (pinfunction "1_1") (pintype "passive"))
      (node (ref "D2") (pin "1") (pinfunction "CATHODE_1") (pintype "bidirectional"))
      (node (ref "IC4") (pin "1") (pinfunction "VIN_1") (pintype "bidirectional"))
      (node (ref "IC4") (pin "3") (pinfunction "CE_3") (pintype "bidirectional"))
      (node (ref "Q1") (pin "2") (pinfunction "S_2") (pintype "bidirectional"))
    )
    (net (code "25") (name "Net-(D3-A)") (class "Default")
      (node (ref "C4") (pin "1") (pinfunction "1_1") (pintype "passive"))
      (node (ref "D3") (pin "2") (pinfunction "A_2") (pintype "bidirectional"))
      (node (ref "D4") (pin "1") (pinfunction "K_1") (pintype "bidirectional"))
    )
    (net (code "26") (name "Net-(D7-CATHODE)") (class "Default")
      (node (ref "D7") (pin "1") (pinfunction "CATHODE_1") (pintype "bidirectional"))
      (node (ref "R_CAPACITOR") (pin "1") (pinfunction "1_1") (pintype "passive"))
    )
    (net (code "27") (name "Net-(EPD_C1-Pad2)") (class "Default")
      (node (ref "EPD_C1") (pin "2") (pinfunction "2_2") (pintype "passive"))
      (node (ref "J1") (pin "4") (pinfunction "4_4") (pintype "bidirectional"))
    )
    (net (code "28") (name "Net-(EPD_C2-Pad2)") (class "Default")
      (node (ref "EPD_C2") (pin "2") (pinfunction "2_2") (pintype "passive"))
      (node (ref "J1") (pin "5") (pinfunction "5_5") (pintype "bidirectional"))
    )
    (net (code "29") (name "Net-(EPD_C6-Pad2)") (class "Default")
      (node (ref "EPD_C6") (pin "2") (pinfunction "2_2") (pintype "passive"))
      (node (ref "J1") (pin "18") (pinfunction "18_18") (pintype "bidirectional"))
    )
    (net (code "30") (name "Net-(EPD_C7-Pad2)") (class "Default")
      (node (ref "EPD_C7") (pin "2") (pinfunction "2_2") (pintype "passive"))
      (node (ref "J1") (pin "19") (pinfunction "19_19") (pintype "bidirectional"))
    )
    (net (code "31") (name "Net-(EPD_C8-Pad2)") (class "Default")
      (node (ref "EPD_C8") (pin "2") (pinfunction "2_2") (pintype "passive"))
      (node (ref "J1") (pin "20") (pinfunction "20_20") (pintype "bidirectional"))
    )
    (net (code "32") (name "Net-(EPD_C10-Pad2)") (class "Default")
      (node (ref "EPD_C10") (pin "2") (pinfunction "2_2") (pintype "passive"))
      (node (ref "J1") (pin "22") (pinfunction "22_22") (pintype "bidirectional"))
    )
    (net (code "33") (name "Net-(EPD_C12-Pad2)") (class "Default")
      (node (ref "EPD_C12") (pin "2") (pinfunction "2_2") (pintype "passive"))
      (node (ref "J1") (pin "24") (pinfunction "24_24") (pintype "bidirectional"))
    )
    (net (code "34") (name "Net-(IC1-CT)") (class "Default")
      (node (ref "C_DELAY") (pin "1") (pinfunction "1_1") (pintype "passive"))
      (node (ref "IC1") (pin "5") (pinfunction "CT_5") (pintype "bidirectional"))
    )
    (net (code "35") (name "Net-(J2-PadA5)") (class "Default")
      (node (ref "J2") (pin "A5") (pinfunction "A5_A5") (pintype "bidirectional"))
      (node (ref "R2-USB1") (pin "2") (pinfunction "2_2") (pintype "passive"))
    )
    (net (code "36") (name "Net-(J2-PadB5)") (class "Default")
      (node (ref "J2") (pin "B5") (pinfunction "B5_B5") (pintype "bidirectional"))
      (node (ref "R2-USB") (pin "1") (pinfunction "1_1") (pintype "passive"))
    )
    (net (code "37") (name "Net-(MCP73831-STAT)") (class "Default")
      (node (ref "MCP73831") (pin "1") (pinfunction "STAT_1") (pintype "output"))
      (node (ref "R1_BAT") (pin "2") (pinfunction "2_2") (pintype "passive"))
    )
    (net (code "38") (name "PREVGH") (class "Default")
      (node (ref "D5") (pin "1") (pinfunction "K_1") (pintype "bidirectional"))
      (node (ref "EPD_C9") (pin "2") (pinfunction "2_2") (pintype "passive"))
      (node (ref "J1") (pin "21") (pinfunction "21_21") (pintype "bidirectional"))
    )
    (net (code "39") (name "PREVGL") (class "Default")
      (node (ref "D4") (pin "2") (pinfunction "A_2") (pintype "bidirectional"))
      (node (ref "EPD_C11") (pin "2") (pinfunction "2_2") (pintype "passive"))
      (node (ref "J1") (pin "23") (pinfunction "23_23") (pintype "bidirectional"))
    )
    (net (code "40") (name "RESE") (class "Default")
      (node (ref "J1") (pin "3") (pinfunction "3_3") (pintype "bidirectional"))
      (node (ref "Q3") (pin "2") (pinfunction "S_2") (pintype "bidirectional"))
      (node (ref "R3") (pin "2") (pinfunction "2_2") (pintype "passive"))
    )
    (net (code "41") (name "RESE'") (class "Default")
      (node (ref "R2") (pin "1") (pinfunction "1_1") (pintype "passive"))
      (node (ref "R3") (pin "1") (pinfunction "1_1") (pintype "passive"))
      (node (ref "SJ1") (pin "2") (pinfunction "2_2") (pintype "passive"))
    )
    (net (code "42") (name "RESET") (class "Default")
      (node (ref "C5") (pin "1") (pinfunction "1_1") (pintype "passive"))
      (node (ref "IC1") (pin "1") (pinfunction "VOUT_1") (pintype "bidirectional"))
      (node (ref "RESET_BUTTON") (pin "3") (pinfunction "3_3") (pintype "passive"))
      (node (ref "RESET_BUTTON") (pin "4") (pinfunction "4_4") (pintype "passive"))
      (node (ref "R_RESET") (pin "1") (pinfunction "1_1") (pintype "passive"))
      (node (ref "U2") (pin "3") (pinfunction "EN_3") (pintype "input"))
    )
    (net (code "43") (name "RTC_RST") (class "Default")
      (node (ref "U2") (pin "16") (pinfunction "IO18_16") (pintype "bidirectional"))
      (node (ref "U3") (pin "4") (pinfunction "~{RST}_4") (pintype "input"))
    )
    (net (code "44") (name "RX") (class "Default")
      (node (ref "TP1") (pin "TP") (pinfunction "TP_TP") (pintype "input"))
      (node (ref "TP2") (pin "TP") (pinfunction "TP_TP") (pintype "input"))
      (node (ref "U2") (pin "24") (pinfunction "RXD0/GPIO17_24") (pintype "bidirectional"))
    )
    (net (code "45") (name "SCK") (class "Default")
      (node (ref "J1") (pin "13") (pinfunction "13_13") (pintype "bidirectional"))
      (node (ref "J4") (pin "P5") (pinfunction "CLK_P5") (pintype "bidirectional"))
      (node (ref "TP8") (pin "TP") (pinfunction "TP_TP") (pintype "input"))
      (node (ref "U1") (pin "6") (pinfunction "CLK_6") (pintype "input"))
      (node (ref "U2") (pin "6") (pinfunction "IO6_6") (pintype "bidirectional"))
    )
    (net (code "46") (name "SCL") (class "Default")
      (node (ref "J3") (pin "4") (pinfunction "4_4") (pintype "passive"))
      (node (ref "R2-PINH") (pin "1") (pinfunction "1_1") (pintype "passive"))
      (node (ref "SENSOR2") (pin "4") (pinfunction "SCK_4") (pintype "input"))
      (node (ref "U2") (pin "20") (pinfunction "IO22_20") (pintype "bidirectional"))
      (node (ref "U3") (pin "16") (pinfunction "SCL_16") (pintype "input"))
      (node (ref "U4") (pin "7") (pinfunction "SCL_7") (pintype "input"))
    )
    (net (code "47") (name "SDA") (class "Default")
      (node (ref "J3") (pin "3") (pinfunction "3_3") (pintype "passive"))
      (node (ref "R1_PINH") (pin "1") (pinfunction "1_1") (pintype "passive"))
      (node (ref "SENSOR2") (pin "3") (pinfunction "SDI_3") (pintype "bidirectional"))
      (node (ref "U2") (pin "19") (pinfunction "IO21_19") (pintype "bidirectional"))
      (node (ref "U3") (pin "15") (pinfunction "SDA_15") (pintype "bidirectional"))
      (node (ref "U4") (pin "8") (pinfunction "SDA_8") (pintype "bidirectional"))
    )
    (net (code "48") (name "SRC") (class "Default")
      (node (ref "C4") (pin "2") (pinfunction "2_2") (pintype "passive"))
      (node (ref "D5") (pin "2") (pinfunction "A_2") (pintype "bidirectional"))
      (node (ref "L1") (pin "1") (pinfunction "1_1") (pintype "passive"))
      (node (ref "Q3") (pin "3") (pinfunction "D_3") (pintype "bidirectional"))
    )
    (net (code "49") (name "SS_SD") (class "Default")
      (node (ref "J4") (pin "P2") (pinfunction "CD/DAT3_P2") (pintype "bidirectional"))
      (node (ref "U2") (pin "4") (pinfunction "IO4_4") (pintype "bidirectional"))
    )
    (net (code "50") (name "TX") (class "Default")
      (node (ref "U2") (pin "25") (pinfunction "TXD0/GPIO16_25") (pintype "bidirectional"))
    )
    (net (code "51") (name "USB_D+") (class "Default")
      (node (ref "D1") (pin "1") (pinfunction "I/O1_1_1") (pintype "bidirectional"))
      (node (ref "U2") (pin "14") (pinfunction "IO13_14") (pintype "bidirectional"))
    )
    (net (code "52") (name "USB_D-") (class "Default")
      (node (ref "D1") (pin "3") (pinfunction "I/O2_1_3") (pintype "bidirectional"))
      (node (ref "U2") (pin "13") (pinfunction "IO12_13") (pintype "bidirectional"))
    )
    (net (code "53") (name "VBAT") (class "Default")
      (node (ref "C2_BAT") (pin "1") (pinfunction "1_1") (pintype "passive"))
      (node (ref "MCP73831") (pin "3") (pinfunction "VBAT_3") (pintype "power_in"))
      (node (ref "MCP73831") (pin "5") (pinfunction "PROG_5") (pintype "input"))
      (node (ref "Q1") (pin "3") (pinfunction "D_3") (pintype "bidirectional"))
      (node (ref "R2_BAT") (pin "2") (pinfunction "2_2") (pintype "passive"))
      (node (ref "TP3") (pin "TP") (pinfunction "TP_TP") (pintype "input"))
      (node (ref "U4") (pin "2") (pinfunction "CELL_2") (pintype "power_in"))
      (node (ref "U4") (pin "3") (pinfunction "VDD_3") (pintype "power_in"))
    )
    (net (code "54") (name "VBUS") (class "Default")
      (node (ref "C2_BAT1") (pin "1") (pinfunction "1_1") (pintype "passive"))
      (node (ref "C4_USB") (pin "1") (pinfunction "1_1") (pintype "passive"))
      (node (ref "C5_USB") (pin "1") (pinfunction "1_1") (pintype "passive"))
      (node (ref "CHG_LED") (pin "A") (pinfunction "A_A") (pintype "passive"))
      (node (ref "D1") (pin "5") (pinfunction "VBUS_5") (pintype "bidirectional"))
      (node (ref "D2") (pin "2") (pinfunction "ANODE_2") (pintype "bidirectional"))
      (node (ref "J2") (pin "A4") (pinfunction "A4_A4") (pintype "bidirectional"))
      (node (ref "MCP73831") (pin "4") (pinfunction "VIN_4") (pintype "power_in"))
      (node (ref "PFMF.050.1") (pin "1") (pinfunction "1_1") (pintype "passive"))
      (node (ref "PFMF.050.1") (pin "2") (pinfunction "2_2") (pintype "passive"))
      (node (ref "Q1") (pin "1") (pinfunction "G_1") (pintype "bidirectional"))
      (node (ref "R1_PWRUSB") (pin "2") (pinfunction "2_2") (pintype "passive"))
      (node (ref "TP14") (pin "TP") (pinfunction "TP_TP") (pintype "input"))
    )
    (net (code "55") (name "VRTC") (class "Default")
      (node (ref "C10_SUPERCAP") (pin "2") (pinfunction "2_2") (pintype "passive"))
      (node (ref "C8") (pin "1") (pinfunction "1_1") (pintype "passive"))
      (node (ref "R_CAPACITOR") (pin "2") (pinfunction "2_2") (pintype "passive"))
      (node (ref "U3") (pin "14") (pinfunction "VBAT_14") (pintype "power_in"))
    )
    (net (code "56") (name "VUSB") (class "Default")
      (node (ref "J2") (pin "A9") (pinfunction "A9_A9") (pintype "bidirectional"))
      (node (ref "J2") (pin "B4") (pinfunction "B4_B4") (pintype "bidirectional"))
      (node (ref "J2") (pin "B9") (pinfunction "B9_B9") (pintype "bidirectional"))
    )
    (net (code "57") (name "unconnected-(IC1-NC-Pad4)") (class "Default")
      (node (ref "IC1") (pin "4") (pinfunction "NC_4") (pintype "no_connect"))
    )
    (net (code "58") (name "unconnected-(IC4-NC-Pad4)") (class "Default")
      (node (ref "IC4") (pin "4") (pinfunction "NC_4") (pintype "no_connect"))
    )
    (net (code "59") (name "unconnected-(J1-Pad1)") (class "Default")
      (node (ref "J1") (pin "1") (pinfunction "1_1") (pintype "bidirectional"))
    )
    (net (code "60") (name "unconnected-(J1-Pad6)") (class "Default")
      (node (ref "J1") (pin "6") (pinfunction "6_6") (pintype "bidirectional"))
    )
    (net (code "61") (name "unconnected-(J1-Pad7)") (class "Default")
      (node (ref "J1") (pin "7") (pinfunction "7_7") (pintype "bidirectional"))
    )
    (net (code "62") (name "unconnected-(J2-PadA8)") (class "Default")
      (node (ref "J2") (pin "A8") (pinfunction "A8_A8") (pintype "bidirectional"))
    )
    (net (code "63") (name "unconnected-(J2-PadB8)") (class "Default")
      (node (ref "J2") (pin "B8") (pinfunction "B8_B8") (pintype "bidirectional"))
    )
    (net (code "64") (name "unconnected-(J4-DAT1-PadP8)") (class "Default")
      (node (ref "J4") (pin "P8") (pinfunction "DAT1_P8") (pintype "bidirectional"))
    )
    (net (code "65") (name "unconnected-(J4-DAT2-PadP1)") (class "Default")
      (node (ref "J4") (pin "P1") (pinfunction "DAT2_P1") (pintype "bidirectional"))
    )
    (net (code "66") (name "unconnected-(J4-DETECTION_1-PadS1)") (class "Default")
      (node (ref "J4") (pin "S1") (pinfunction "DETECTION_1_S1") (pintype "bidirectional"))
    )
    (net (code "67") (name "unconnected-(J4-DETECTION_2-PadS2)") (class "Default")
      (node (ref "J4") (pin "S2") (pinfunction "DETECTION_2_S2") (pintype "bidirectional"))
    )
    (net (code "68") (name "unconnected-(U2-NC-Pad22)") (class "Default")
      (node (ref "U2") (pin "22") (pinfunction "NC_22") (pintype "no_connect"))
    )
    (net (code "69") (name "unconnected-(U4-~{ALERT}-Pad5)") (class "Default")
      (node (ref "U4") (pin "5") (pinfunction "~{ALERT}_5") (pintype "output"))
    )
  )
)
